# interface.net
KiCad netlist of a schematic drawn in Altium Designer
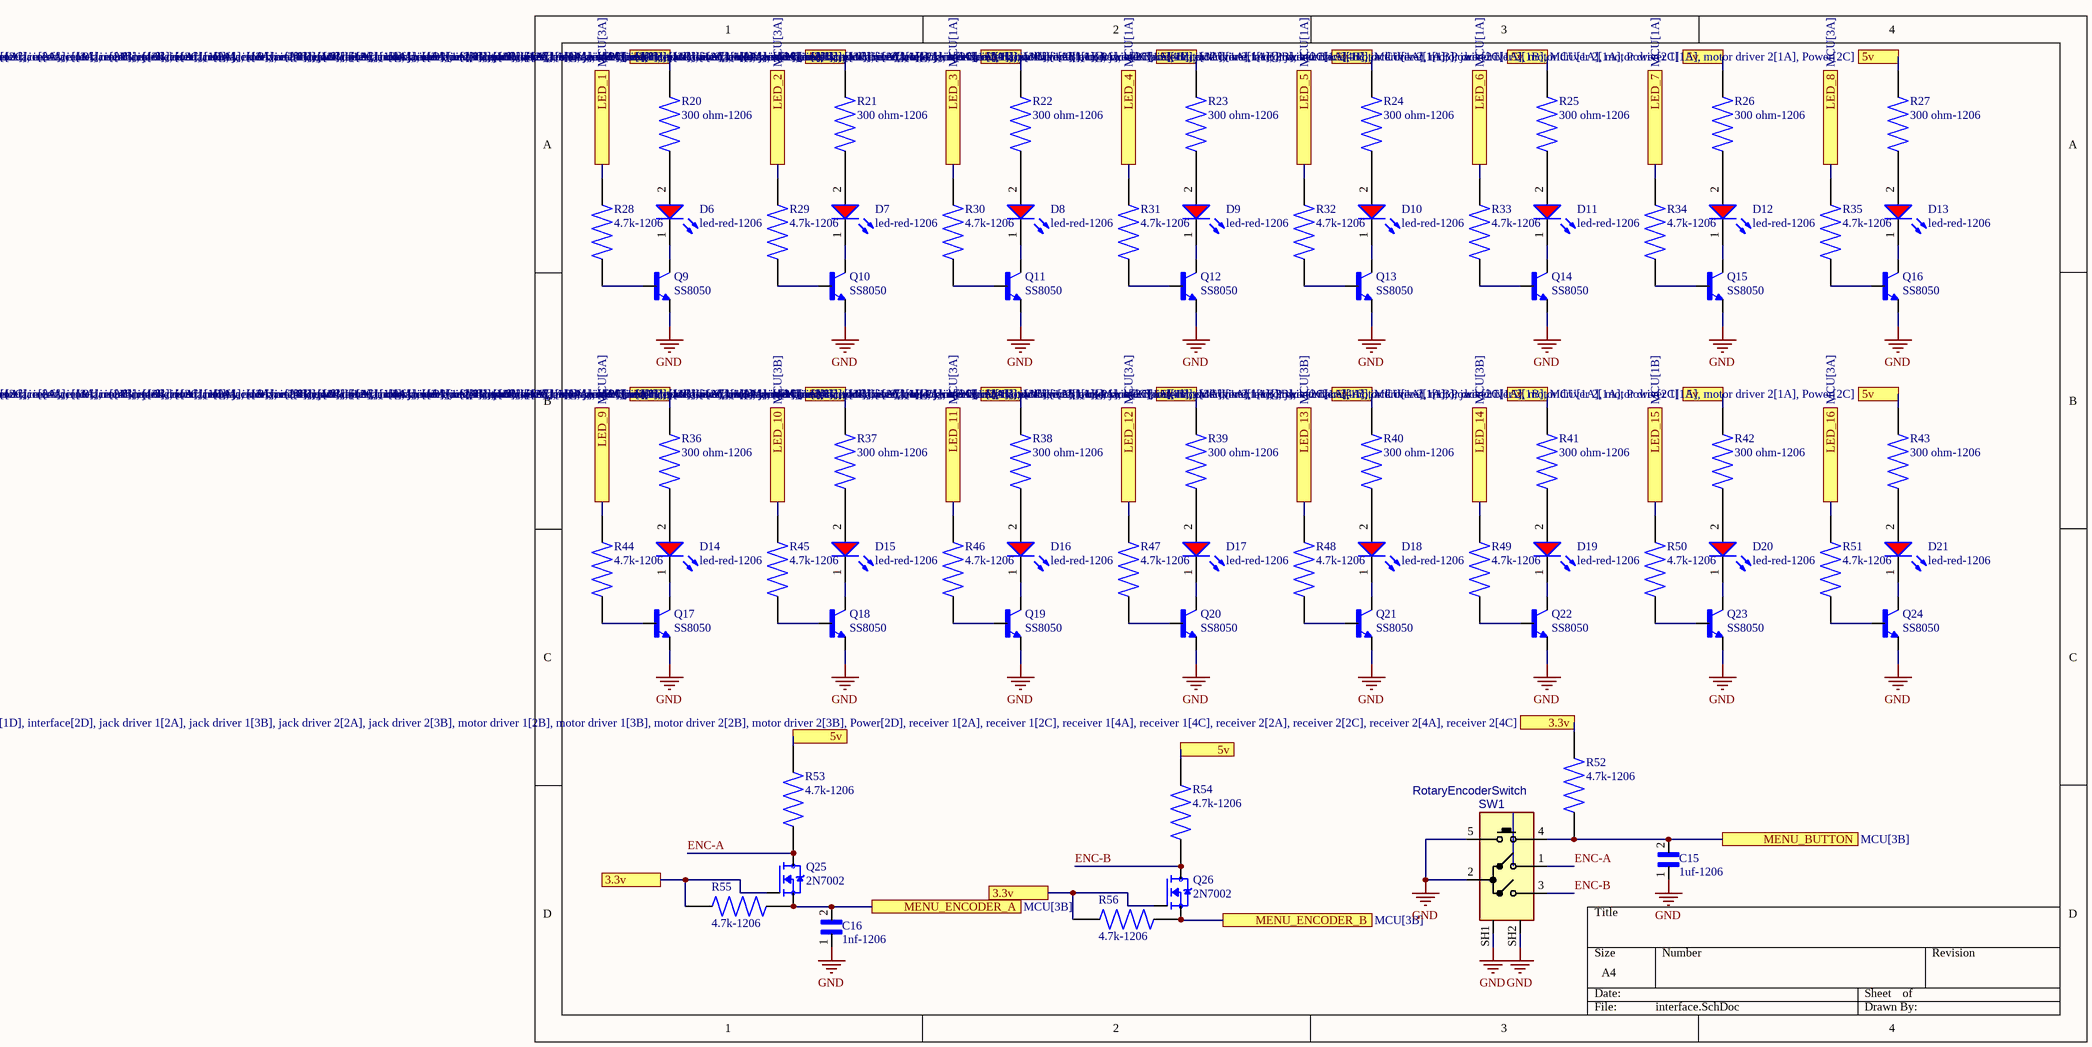
[diagram p0: interface.SchDoc]

(export (version "E")
  (design (tool "Eeschema 10.0.6"))
  (components
    (comp (ref "C15")
      (value "1uf-1206")
      (footprint "CAPC3216X180N")
      (description "1ÂµF Â±20% 50V Ceramic Capacitor X8R 1206 (3216 Metric)")
      (fields (field (name "MF") "TDK") (field (name "MP") "CGA5L3X8R1H105M160AB"))
      (libsource (lib "cap-1206") (part "CGA5L3X8R1H105M160AB"))
    )
    (comp (ref "C16")
      (value "1nf-1206")
      (footprint "CAPC3216X180N")
      (description "1ÂµF Â±20% 50V Ceramic Capacitor X8R 1206 (3216 Metric)")
      (fields (field (name "MF") "TDK") (field (name "MP") "CGA5L3X8R1H105M160AB"))
      (libsource (lib "cap-1206") (part "CGA5L3X8R1H105M160AB"))
    )
    (comp (ref "D6")
      (value "led-red-1206")
      (footprint "WL-SMRW_1206 dome_normal use")
      (description "WL-SMRW Mono-color Reverse mount Waterclear, SMT, size 1206 dome, Red, 2V, 20°")
      (fields
        (field (name "MANUFACTURER PART NUMBER") "156120RS82500")
        (field (name "MANUFACTURER") "Wurth Elektronik")
      )
      (libsource (lib "led-1206") (part "156120RS82500"))
    )
    (comp (ref "D7")
      (value "led-red-1206")
      (footprint "WL-SMRW_1206 dome_normal use")
      (description "WL-SMRW Mono-color Reverse mount Waterclear, SMT, size 1206 dome, Red, 2V, 20°")
      (fields
        (field (name "MANUFACTURER PART NUMBER") "156120RS82500")
        (field (name "MANUFACTURER") "Wurth Elektronik")
      )
      (libsource (lib "led-1206") (part "156120RS82500"))
    )
    (comp (ref "D8")
      (value "led-red-1206")
      (footprint "WL-SMRW_1206 dome_normal use")
      (description "WL-SMRW Mono-color Reverse mount Waterclear, SMT, size 1206 dome, Red, 2V, 20°")
      (fields
        (field (name "MANUFACTURER PART NUMBER") "156120RS82500")
        (field (name "MANUFACTURER") "Wurth Elektronik")
      )
      (libsource (lib "led-1206") (part "156120RS82500"))
    )
    (comp (ref "D9")
      (value "led-red-1206")
      (footprint "WL-SMRW_1206 dome_normal use")
      (description "WL-SMRW Mono-color Reverse mount Waterclear, SMT, size 1206 dome, Red, 2V, 20°")
      (fields
        (field (name "MANUFACTURER PART NUMBER") "156120RS82500")
        (field (name "MANUFACTURER") "Wurth Elektronik")
      )
      (libsource (lib "led-1206") (part "156120RS82500"))
    )
    (comp (ref "D10")
      (value "led-red-1206")
      (footprint "WL-SMRW_1206 dome_normal use")
      (description "WL-SMRW Mono-color Reverse mount Waterclear, SMT, size 1206 dome, Red, 2V, 20°")
      (fields
        (field (name "MANUFACTURER PART NUMBER") "156120RS82500")
        (field (name "MANUFACTURER") "Wurth Elektronik")
      )
      (libsource (lib "led-1206") (part "156120RS82500"))
    )
    (comp (ref "D11")
      (value "led-red-1206")
      (footprint "WL-SMRW_1206 dome_normal use")
      (description "WL-SMRW Mono-color Reverse mount Waterclear, SMT, size 1206 dome, Red, 2V, 20°")
      (fields
        (field (name "MANUFACTURER PART NUMBER") "156120RS82500")
        (field (name "MANUFACTURER") "Wurth Elektronik")
      )
      (libsource (lib "led-1206") (part "156120RS82500"))
    )
    (comp (ref "D12")
      (value "led-red-1206")
      (footprint "WL-SMRW_1206 dome_normal use")
      (description "WL-SMRW Mono-color Reverse mount Waterclear, SMT, size 1206 dome, Red, 2V, 20°")
      (fields
        (field (name "MANUFACTURER PART NUMBER") "156120RS82500")
        (field (name "MANUFACTURER") "Wurth Elektronik")
      )
      (libsource (lib "led-1206") (part "156120RS82500"))
    )
    (comp (ref "D13")
      (value "led-red-1206")
      (footprint "WL-SMRW_1206 dome_normal use")
      (description "WL-SMRW Mono-color Reverse mount Waterclear, SMT, size 1206 dome, Red, 2V, 20°")
      (fields
        (field (name "MANUFACTURER PART NUMBER") "156120RS82500")
        (field (name "MANUFACTURER") "Wurth Elektronik")
      )
      (libsource (lib "led-1206") (part "156120RS82500"))
    )
    (comp (ref "D14")
      (value "led-red-1206")
      (footprint "WL-SMRW_1206 dome_normal use")
      (description "WL-SMRW Mono-color Reverse mount Waterclear, SMT, size 1206 dome, Red, 2V, 20°")
      (fields
        (field (name "MANUFACTURER PART NUMBER") "156120RS82500")
        (field (name "MANUFACTURER") "Wurth Elektronik")
      )
      (libsource (lib "led-1206") (part "156120RS82500"))
    )
    (comp (ref "D15")
      (value "led-red-1206")
      (footprint "WL-SMRW_1206 dome_normal use")
      (description "WL-SMRW Mono-color Reverse mount Waterclear, SMT, size 1206 dome, Red, 2V, 20°")
      (fields
        (field (name "MANUFACTURER PART NUMBER") "156120RS82500")
        (field (name "MANUFACTURER") "Wurth Elektronik")
      )
      (libsource (lib "led-1206") (part "156120RS82500"))
    )
    (comp (ref "D16")
      (value "led-red-1206")
      (footprint "WL-SMRW_1206 dome_normal use")
      (description "WL-SMRW Mono-color Reverse mount Waterclear, SMT, size 1206 dome, Red, 2V, 20°")
      (fields
        (field (name "MANUFACTURER PART NUMBER") "156120RS82500")
        (field (name "MANUFACTURER") "Wurth Elektronik")
      )
      (libsource (lib "led-1206") (part "156120RS82500"))
    )
    (comp (ref "D17")
      (value "led-red-1206")
      (footprint "WL-SMRW_1206 dome_normal use")
      (description "WL-SMRW Mono-color Reverse mount Waterclear, SMT, size 1206 dome, Red, 2V, 20°")
      (fields
        (field (name "MANUFACTURER PART NUMBER") "156120RS82500")
        (field (name "MANUFACTURER") "Wurth Elektronik")
      )
      (libsource (lib "led-1206") (part "156120RS82500"))
    )
    (comp (ref "D18")
      (value "led-red-1206")
      (footprint "WL-SMRW_1206 dome_normal use")
      (description "WL-SMRW Mono-color Reverse mount Waterclear, SMT, size 1206 dome, Red, 2V, 20°")
      (fields
        (field (name "MANUFACTURER PART NUMBER") "156120RS82500")
        (field (name "MANUFACTURER") "Wurth Elektronik")
      )
      (libsource (lib "led-1206") (part "156120RS82500"))
    )
    (comp (ref "D19")
      (value "led-red-1206")
      (footprint "WL-SMRW_1206 dome_normal use")
      (description "WL-SMRW Mono-color Reverse mount Waterclear, SMT, size 1206 dome, Red, 2V, 20°")
      (fields
        (field (name "MANUFACTURER PART NUMBER") "156120RS82500")
        (field (name "MANUFACTURER") "Wurth Elektronik")
      )
      (libsource (lib "led-1206") (part "156120RS82500"))
    )
    (comp (ref "D20")
      (value "led-red-1206")
      (footprint "WL-SMRW_1206 dome_normal use")
      (description "WL-SMRW Mono-color Reverse mount Waterclear, SMT, size 1206 dome, Red, 2V, 20°")
      (fields
        (field (name "MANUFACTURER PART NUMBER") "156120RS82500")
        (field (name "MANUFACTURER") "Wurth Elektronik")
      )
      (libsource (lib "led-1206") (part "156120RS82500"))
    )
    (comp (ref "D21")
      (value "led-red-1206")
      (footprint "WL-SMRW_1206 dome_normal use")
      (description "WL-SMRW Mono-color Reverse mount Waterclear, SMT, size 1206 dome, Red, 2V, 20°")
      (fields
        (field (name "MANUFACTURER PART NUMBER") "156120RS82500")
        (field (name "MANUFACTURER") "Wurth Elektronik")
      )
      (libsource (lib "led-1206") (part "156120RS82500"))
    )
    (comp (ref "Q9")
      (value "SS8050")
      (footprint "TRANS_SS8050-G")
      (description "Bipolar (BJT) Transistor NPN 25 V 1.5 A 100MHz 300 mW Surface Mount SOT-23-3")
      (fields (field (name "DIGI-KEY_PART_NUMBER") "641-1790-2-ND") (field (name "MP") "SS8050G"))
      (libsource (lib "SS8050-G") (part "SS8050-G"))
    )
    (comp (ref "Q10")
      (value "SS8050")
      (footprint "TRANS_SS8050-G")
      (description "Bipolar (BJT) Transistor NPN 25 V 1.5 A 100MHz 300 mW Surface Mount SOT-23-3")
      (fields (field (name "DIGI-KEY_PART_NUMBER") "641-1790-2-ND") (field (name "MP") "SS8050G"))
      (libsource (lib "SS8050-G") (part "SS8050-G"))
    )
    (comp (ref "Q11")
      (value "SS8050")
      (footprint "TRANS_SS8050-G")
      (description "Bipolar (BJT) Transistor NPN 25 V 1.5 A 100MHz 300 mW Surface Mount SOT-23-3")
      (fields (field (name "DIGI-KEY_PART_NUMBER") "641-1790-2-ND") (field (name "MP") "SS8050G"))
      (libsource (lib "SS8050-G") (part "SS8050-G"))
    )
    (comp (ref "Q12")
      (value "SS8050")
      (footprint "TRANS_SS8050-G")
      (description "Bipolar (BJT) Transistor NPN 25 V 1.5 A 100MHz 300 mW Surface Mount SOT-23-3")
      (fields (field (name "DIGI-KEY_PART_NUMBER") "641-1790-2-ND") (field (name "MP") "SS8050G"))
      (libsource (lib "SS8050-G") (part "SS8050-G"))
    )
    (comp (ref "Q13")
      (value "SS8050")
      (footprint "TRANS_SS8050-G")
      (description "Bipolar (BJT) Transistor NPN 25 V 1.5 A 100MHz 300 mW Surface Mount SOT-23-3")
      (fields (field (name "DIGI-KEY_PART_NUMBER") "641-1790-2-ND") (field (name "MP") "SS8050G"))
      (libsource (lib "SS8050-G") (part "SS8050-G"))
    )
    (comp (ref "Q14")
      (value "SS8050")
      (footprint "TRANS_SS8050-G")
      (description "Bipolar (BJT) Transistor NPN 25 V 1.5 A 100MHz 300 mW Surface Mount SOT-23-3")
      (fields (field (name "DIGI-KEY_PART_NUMBER") "641-1790-2-ND") (field (name "MP") "SS8050G"))
      (libsource (lib "SS8050-G") (part "SS8050-G"))
    )
    (comp (ref "Q15")
      (value "SS8050")
      (footprint "TRANS_SS8050-G")
      (description "Bipolar (BJT) Transistor NPN 25 V 1.5 A 100MHz 300 mW Surface Mount SOT-23-3")
      (fields (field (name "DIGI-KEY_PART_NUMBER") "641-1790-2-ND") (field (name "MP") "SS8050G"))
      (libsource (lib "SS8050-G") (part "SS8050-G"))
    )
    (comp (ref "Q16")
      (value "SS8050")
      (footprint "TRANS_SS8050-G")
      (description "Bipolar (BJT) Transistor NPN 25 V 1.5 A 100MHz 300 mW Surface Mount SOT-23-3")
      (fields (field (name "DIGI-KEY_PART_NUMBER") "641-1790-2-ND") (field (name "MP") "SS8050G"))
      (libsource (lib "SS8050-G") (part "SS8050-G"))
    )
    (comp (ref "Q17")
      (value "SS8050")
      (footprint "TRANS_SS8050-G")
      (description "Bipolar (BJT) Transistor NPN 25 V 1.5 A 100MHz 300 mW Surface Mount SOT-23-3")
      (fields (field (name "DIGI-KEY_PART_NUMBER") "641-1790-2-ND") (field (name "MP") "SS8050G"))
      (libsource (lib "SS8050-G") (part "SS8050-G"))
    )
    (comp (ref "Q18")
      (value "SS8050")
      (footprint "TRANS_SS8050-G")
      (description "Bipolar (BJT) Transistor NPN 25 V 1.5 A 100MHz 300 mW Surface Mount SOT-23-3")
      (fields (field (name "DIGI-KEY_PART_NUMBER") "641-1790-2-ND") (field (name "MP") "SS8050G"))
      (libsource (lib "SS8050-G") (part "SS8050-G"))
    )
    (comp (ref "Q19")
      (value "SS8050")
      (footprint "TRANS_SS8050-G")
      (description "Bipolar (BJT) Transistor NPN 25 V 1.5 A 100MHz 300 mW Surface Mount SOT-23-3")
      (fields (field (name "DIGI-KEY_PART_NUMBER") "641-1790-2-ND") (field (name "MP") "SS8050G"))
      (libsource (lib "SS8050-G") (part "SS8050-G"))
    )
    (comp (ref "Q20")
      (value "SS8050")
      (footprint "TRANS_SS8050-G")
      (description "Bipolar (BJT) Transistor NPN 25 V 1.5 A 100MHz 300 mW Surface Mount SOT-23-3")
      (fields (field (name "DIGI-KEY_PART_NUMBER") "641-1790-2-ND") (field (name "MP") "SS8050G"))
      (libsource (lib "SS8050-G") (part "SS8050-G"))
    )
    (comp (ref "Q21")
      (value "SS8050")
      (footprint "TRANS_SS8050-G")
      (description "Bipolar (BJT) Transistor NPN 25 V 1.5 A 100MHz 300 mW Surface Mount SOT-23-3")
      (fields (field (name "DIGI-KEY_PART_NUMBER") "641-1790-2-ND") (field (name "MP") "SS8050G"))
      (libsource (lib "SS8050-G") (part "SS8050-G"))
    )
    (comp (ref "Q22")
      (value "SS8050")
      (footprint "TRANS_SS8050-G")
      (description "Bipolar (BJT) Transistor NPN 25 V 1.5 A 100MHz 300 mW Surface Mount SOT-23-3")
      (fields (field (name "DIGI-KEY_PART_NUMBER") "641-1790-2-ND") (field (name "MP") "SS8050G"))
      (libsource (lib "SS8050-G") (part "SS8050-G"))
    )
    (comp (ref "Q23")
      (value "SS8050")
      (footprint "TRANS_SS8050-G")
      (description "Bipolar (BJT) Transistor NPN 25 V 1.5 A 100MHz 300 mW Surface Mount SOT-23-3")
      (fields (field (name "DIGI-KEY_PART_NUMBER") "641-1790-2-ND") (field (name "MP") "SS8050G"))
      (libsource (lib "SS8050-G") (part "SS8050-G"))
    )
    (comp (ref "Q24")
      (value "SS8050")
      (footprint "TRANS_SS8050-G")
      (description "Bipolar (BJT) Transistor NPN 25 V 1.5 A 100MHz 300 mW Surface Mount SOT-23-3")
      (fields (field (name "DIGI-KEY_PART_NUMBER") "641-1790-2-ND") (field (name "MP") "SS8050G"))
      (libsource (lib "SS8050-G") (part "SS8050-G"))
    )
    (comp (ref "Q25")
      (value "2N7002")
      (footprint "SOT95P240X111-3N")
      (description "N-Channel 60V 280mA (Ta) 350mW (Ta) Surface Mount SOT-23-3 (TO-236)")
      (fields (field (name "MF") "{'manufacturer': u'onsemi'}"))
      (libsource (lib "2N7002-SOT23") (part "2N7002"))
    )
    (comp (ref "Q26")
      (value "2N7002")
      (footprint "SOT95P240X111-3N")
      (description "N-Channel 60V 280mA (Ta) 350mW (Ta) Surface Mount SOT-23-3 (TO-236)")
      (fields (field (name "MF") "{'manufacturer': u'onsemi'}"))
      (libsource (lib "2N7002-SOT23") (part "2N7002"))
    )
    (comp (ref "R20")
      (value "300 ohm-1206")
      (footprint "RESC3015X65N")
      (description "Res Thin Film 1206 10K Ohm 0.1% 1/8W Â±25ppm/Â°C Molded SMD SMD Paper T/R")
      (fields (field (name "MF") "TE Connectivity") (field (name "MP") "CPF1206B10KE1"))
      (libsource (lib "resistor-1206") (part "CPF1206B10KE1"))
    )
    (comp (ref "R21")
      (value "300 ohm-1206")
      (footprint "RESC3015X65N")
      (description "Res Thin Film 1206 10K Ohm 0.1% 1/8W Â±25ppm/Â°C Molded SMD SMD Paper T/R")
      (fields (field (name "MF") "TE Connectivity") (field (name "MP") "CPF1206B10KE1"))
      (libsource (lib "resistor-1206") (part "CPF1206B10KE1"))
    )
    (comp (ref "R22")
      (value "300 ohm-1206")
      (footprint "RESC3015X65N")
      (description "Res Thin Film 1206 10K Ohm 0.1% 1/8W Â±25ppm/Â°C Molded SMD SMD Paper T/R")
      (fields (field (name "MF") "TE Connectivity") (field (name "MP") "CPF1206B10KE1"))
      (libsource (lib "resistor-1206") (part "CPF1206B10KE1"))
    )
    (comp (ref "R23")
      (value "300 ohm-1206")
      (footprint "RESC3015X65N")
      (description "Res Thin Film 1206 10K Ohm 0.1% 1/8W Â±25ppm/Â°C Molded SMD SMD Paper T/R")
      (fields (field (name "MF") "TE Connectivity") (field (name "MP") "CPF1206B10KE1"))
      (libsource (lib "resistor-1206") (part "CPF1206B10KE1"))
    )
    (comp (ref "R24")
      (value "300 ohm-1206")
      (footprint "RESC3015X65N")
      (description "Res Thin Film 1206 10K Ohm 0.1% 1/8W Â±25ppm/Â°C Molded SMD SMD Paper T/R")
      (fields (field (name "MF") "TE Connectivity") (field (name "MP") "CPF1206B10KE1"))
      (libsource (lib "resistor-1206") (part "CPF1206B10KE1"))
    )
    (comp (ref "R25")
      (value "300 ohm-1206")
      (footprint "RESC3015X65N")
      (description "Res Thin Film 1206 10K Ohm 0.1% 1/8W Â±25ppm/Â°C Molded SMD SMD Paper T/R")
      (fields (field (name "MF") "TE Connectivity") (field (name "MP") "CPF1206B10KE1"))
      (libsource (lib "resistor-1206") (part "CPF1206B10KE1"))
    )
    (comp (ref "R26")
      (value "300 ohm-1206")
      (footprint "RESC3015X65N")
      (description "Res Thin Film 1206 10K Ohm 0.1% 1/8W Â±25ppm/Â°C Molded SMD SMD Paper T/R")
      (fields (field (name "MF") "TE Connectivity") (field (name "MP") "CPF1206B10KE1"))
      (libsource (lib "resistor-1206") (part "CPF1206B10KE1"))
    )
    (comp (ref "R27")
      (value "300 ohm-1206")
      (footprint "RESC3015X65N")
      (description "Res Thin Film 1206 10K Ohm 0.1% 1/8W Â±25ppm/Â°C Molded SMD SMD Paper T/R")
      (fields (field (name "MF") "TE Connectivity") (field (name "MP") "CPF1206B10KE1"))
      (libsource (lib "resistor-1206") (part "CPF1206B10KE1"))
    )
    (comp (ref "R28")
      (value "4.7k-1206")
      (footprint "RESC3015X65N")
      (description "Res Thin Film 1206 10K Ohm 0.1% 1/8W Â±25ppm/Â°C Molded SMD SMD Paper T/R")
      (fields (field (name "MF") "TE Connectivity") (field (name "MP") "CPF1206B10KE1"))
      (libsource (lib "resistor-1206") (part "CPF1206B10KE1"))
    )
    (comp (ref "R29")
      (value "4.7k-1206")
      (footprint "RESC3015X65N")
      (description "Res Thin Film 1206 10K Ohm 0.1% 1/8W Â±25ppm/Â°C Molded SMD SMD Paper T/R")
      (fields (field (name "MF") "TE Connectivity") (field (name "MP") "CPF1206B10KE1"))
      (libsource (lib "resistor-1206") (part "CPF1206B10KE1"))
    )
    (comp (ref "R30")
      (value "4.7k-1206")
      (footprint "RESC3015X65N")
      (description "Res Thin Film 1206 10K Ohm 0.1% 1/8W Â±25ppm/Â°C Molded SMD SMD Paper T/R")
      (fields (field (name "MF") "TE Connectivity") (field (name "MP") "CPF1206B10KE1"))
      (libsource (lib "resistor-1206") (part "CPF1206B10KE1"))
    )
    (comp (ref "R31")
      (value "4.7k-1206")
      (footprint "RESC3015X65N")
      (description "Res Thin Film 1206 10K Ohm 0.1% 1/8W Â±25ppm/Â°C Molded SMD SMD Paper T/R")
      (fields (field (name "MF") "TE Connectivity") (field (name "MP") "CPF1206B10KE1"))
      (libsource (lib "resistor-1206") (part "CPF1206B10KE1"))
    )
    (comp (ref "R32")
      (value "4.7k-1206")
      (footprint "RESC3015X65N")
      (description "Res Thin Film 1206 10K Ohm 0.1% 1/8W Â±25ppm/Â°C Molded SMD SMD Paper T/R")
      (fields (field (name "MF") "TE Connectivity") (field (name "MP") "CPF1206B10KE1"))
      (libsource (lib "resistor-1206") (part "CPF1206B10KE1"))
    )
    (comp (ref "R33")
      (value "4.7k-1206")
      (footprint "RESC3015X65N")
      (description "Res Thin Film 1206 10K Ohm 0.1% 1/8W Â±25ppm/Â°C Molded SMD SMD Paper T/R")
      (fields (field (name "MF") "TE Connectivity") (field (name "MP") "CPF1206B10KE1"))
      (libsource (lib "resistor-1206") (part "CPF1206B10KE1"))
    )
    (comp (ref "R34")
      (value "4.7k-1206")
      (footprint "RESC3015X65N")
      (description "Res Thin Film 1206 10K Ohm 0.1% 1/8W Â±25ppm/Â°C Molded SMD SMD Paper T/R")
      (fields (field (name "MF") "TE Connectivity") (field (name "MP") "CPF1206B10KE1"))
      (libsource (lib "resistor-1206") (part "CPF1206B10KE1"))
    )
    (comp (ref "R35")
      (value "4.7k-1206")
      (footprint "RESC3015X65N")
      (description "Res Thin Film 1206 10K Ohm 0.1% 1/8W Â±25ppm/Â°C Molded SMD SMD Paper T/R")
      (fields (field (name "MF") "TE Connectivity") (field (name "MP") "CPF1206B10KE1"))
      (libsource (lib "resistor-1206") (part "CPF1206B10KE1"))
    )
    (comp (ref "R36")
      (value "300 ohm-1206")
      (footprint "RESC3015X65N")
      (description "Res Thin Film 1206 10K Ohm 0.1% 1/8W Â±25ppm/Â°C Molded SMD SMD Paper T/R")
      (fields (field (name "MF") "TE Connectivity") (field (name "MP") "CPF1206B10KE1"))
      (libsource (lib "resistor-1206") (part "CPF1206B10KE1"))
    )
    (comp (ref "R37")
      (value "300 ohm-1206")
      (footprint "RESC3015X65N")
      (description "Res Thin Film 1206 10K Ohm 0.1% 1/8W Â±25ppm/Â°C Molded SMD SMD Paper T/R")
      (fields (field (name "MF") "TE Connectivity") (field (name "MP") "CPF1206B10KE1"))
      (libsource (lib "resistor-1206") (part "CPF1206B10KE1"))
    )
    (comp (ref "R38")
      (value "300 ohm-1206")
      (footprint "RESC3015X65N")
      (description "Res Thin Film 1206 10K Ohm 0.1% 1/8W Â±25ppm/Â°C Molded SMD SMD Paper T/R")
      (fields (field (name "MF") "TE Connectivity") (field (name "MP") "CPF1206B10KE1"))
      (libsource (lib "resistor-1206") (part "CPF1206B10KE1"))
    )
    (comp (ref "R39")
      (value "300 ohm-1206")
      (footprint "RESC3015X65N")
      (description "Res Thin Film 1206 10K Ohm 0.1% 1/8W Â±25ppm/Â°C Molded SMD SMD Paper T/R")
      (fields (field (name "MF") "TE Connectivity") (field (name "MP") "CPF1206B10KE1"))
      (libsource (lib "resistor-1206") (part "CPF1206B10KE1"))
    )
    (comp (ref "R40")
      (value "300 ohm-1206")
      (footprint "RESC3015X65N")
      (description "Res Thin Film 1206 10K Ohm 0.1% 1/8W Â±25ppm/Â°C Molded SMD SMD Paper T/R")
      (fields (field (name "MF") "TE Connectivity") (field (name "MP") "CPF1206B10KE1"))
      (libsource (lib "resistor-1206") (part "CPF1206B10KE1"))
    )
    (comp (ref "R41")
      (value "300 ohm-1206")
      (footprint "RESC3015X65N")
      (description "Res Thin Film 1206 10K Ohm 0.1% 1/8W Â±25ppm/Â°C Molded SMD SMD Paper T/R")
      (fields (field (name "MF") "TE Connectivity") (field (name "MP") "CPF1206B10KE1"))
      (libsource (lib "resistor-1206") (part "CPF1206B10KE1"))
    )
    (comp (ref "R42")
      (value "300 ohm-1206")
      (footprint "RESC3015X65N")
      (description "Res Thin Film 1206 10K Ohm 0.1% 1/8W Â±25ppm/Â°C Molded SMD SMD Paper T/R")
      (fields (field (name "MF") "TE Connectivity") (field (name "MP") "CPF1206B10KE1"))
      (libsource (lib "resistor-1206") (part "CPF1206B10KE1"))
    )
    (comp (ref "R43")
      (value "300 ohm-1206")
      (footprint "RESC3015X65N")
      (description "Res Thin Film 1206 10K Ohm 0.1% 1/8W Â±25ppm/Â°C Molded SMD SMD Paper T/R")
      (fields (field (name "MF") "TE Connectivity") (field (name "MP") "CPF1206B10KE1"))
      (libsource (lib "resistor-1206") (part "CPF1206B10KE1"))
    )
    (comp (ref "R44")
      (value "4.7k-1206")
      (footprint "RESC3015X65N")
      (description "Res Thin Film 1206 10K Ohm 0.1% 1/8W Â±25ppm/Â°C Molded SMD SMD Paper T/R")
      (fields (field (name "MF") "TE Connectivity") (field (name "MP") "CPF1206B10KE1"))
      (libsource (lib "resistor-1206") (part "CPF1206B10KE1"))
    )
    (comp (ref "R45")
      (value "4.7k-1206")
      (footprint "RESC3015X65N")
      (description "Res Thin Film 1206 10K Ohm 0.1% 1/8W Â±25ppm/Â°C Molded SMD SMD Paper T/R")
      (fields (field (name "MF") "TE Connectivity") (field (name "MP") "CPF1206B10KE1"))
      (libsource (lib "resistor-1206") (part "CPF1206B10KE1"))
    )
    (comp (ref "R46")
      (value "4.7k-1206")
      (footprint "RESC3015X65N")
      (description "Res Thin Film 1206 10K Ohm 0.1% 1/8W Â±25ppm/Â°C Molded SMD SMD Paper T/R")
      (fields (field (name "MF") "TE Connectivity") (field (name "MP") "CPF1206B10KE1"))
      (libsource (lib "resistor-1206") (part "CPF1206B10KE1"))
    )
    (comp (ref "R47")
      (value "4.7k-1206")
      (footprint "RESC3015X65N")
      (description "Res Thin Film 1206 10K Ohm 0.1% 1/8W Â±25ppm/Â°C Molded SMD SMD Paper T/R")
      (fields (field (name "MF") "TE Connectivity") (field (name "MP") "CPF1206B10KE1"))
      (libsource (lib "resistor-1206") (part "CPF1206B10KE1"))
    )
    (comp (ref "R48")
      (value "4.7k-1206")
      (footprint "RESC3015X65N")
      (description "Res Thin Film 1206 10K Ohm 0.1% 1/8W Â±25ppm/Â°C Molded SMD SMD Paper T/R")
      (fields (field (name "MF") "TE Connectivity") (field (name "MP") "CPF1206B10KE1"))
      (libsource (lib "resistor-1206") (part "CPF1206B10KE1"))
    )
    (comp (ref "R49")
      (value "4.7k-1206")
      (footprint "RESC3015X65N")
      (description "Res Thin Film 1206 10K Ohm 0.1% 1/8W Â±25ppm/Â°C Molded SMD SMD Paper T/R")
      (fields (field (name "MF") "TE Connectivity") (field (name "MP") "CPF1206B10KE1"))
      (libsource (lib "resistor-1206") (part "CPF1206B10KE1"))
    )
    (comp (ref "R50")
      (value "4.7k-1206")
      (footprint "RESC3015X65N")
      (description "Res Thin Film 1206 10K Ohm 0.1% 1/8W Â±25ppm/Â°C Molded SMD SMD Paper T/R")
      (fields (field (name "MF") "TE Connectivity") (field (name "MP") "CPF1206B10KE1"))
      (libsource (lib "resistor-1206") (part "CPF1206B10KE1"))
    )
    (comp (ref "R51")
      (value "4.7k-1206")
      (footprint "RESC3015X65N")
      (description "Res Thin Film 1206 10K Ohm 0.1% 1/8W Â±25ppm/Â°C Molded SMD SMD Paper T/R")
      (fields (field (name "MF") "TE Connectivity") (field (name "MP") "CPF1206B10KE1"))
      (libsource (lib "resistor-1206") (part "CPF1206B10KE1"))
    )
    (comp (ref "R52")
      (value "4.7k-1206")
      (footprint "RESC3015X65N")
      (description "Res Thin Film 1206 10K Ohm 0.1% 1/8W Â±25ppm/Â°C Molded SMD SMD Paper T/R")
      (fields (field (name "MF") "TE Connectivity") (field (name "MP") "CPF1206B10KE1"))
      (libsource (lib "resistor-1206") (part "CPF1206B10KE1"))
    )
    (comp (ref "R53")
      (value "4.7k-1206")
      (footprint "RESC3015X65N")
      (description "Res Thin Film 1206 10K Ohm 0.1% 1/8W Â±25ppm/Â°C Molded SMD SMD Paper T/R")
      (fields (field (name "MF") "TE Connectivity") (field (name "MP") "CPF1206B10KE1"))
      (libsource (lib "resistor-1206") (part "CPF1206B10KE1"))
    )
    (comp (ref "R54")
      (value "4.7k-1206")
      (footprint "RESC3015X65N")
      (description "Res Thin Film 1206 10K Ohm 0.1% 1/8W Â±25ppm/Â°C Molded SMD SMD Paper T/R")
      (fields (field (name "MF") "TE Connectivity") (field (name "MP") "CPF1206B10KE1"))
      (libsource (lib "resistor-1206") (part "CPF1206B10KE1"))
    )
    (comp (ref "R55")
      (value "4.7k-1206")
      (footprint "RESC3015X65N")
      (description "Res Thin Film 1206 10K Ohm 0.1% 1/8W Â±25ppm/Â°C Molded SMD SMD Paper T/R")
      (fields (field (name "MF") "TE Connectivity") (field (name "MP") "CPF1206B10KE1"))
      (libsource (lib "resistor-1206") (part "CPF1206B10KE1"))
    )
    (comp (ref "R56")
      (value "4.7k-1206")
      (footprint "RESC3015X65N")
      (description "Res Thin Film 1206 10K Ohm 0.1% 1/8W Â±25ppm/Â°C Molded SMD SMD Paper T/R")
      (fields (field (name "MF") "TE Connectivity") (field (name "MP") "CPF1206B10KE1"))
      (libsource (lib "resistor-1206") (part "CPF1206B10KE1"))
    )
    (comp (ref "SW1")
      (value "RotaryEncoderSwitch")
      (footprint "SWROT_11MM")
      (description "SWITCH, ROTARY Encoder, 11mm Metal Shaft")
      (fields (field (name "MANF") "Alpha") (field (name "MANF_PART#") "RE111F-41B3N-15F-20P"))
      (libsource (lib "rotary encoder") (part "SWROT_11MM"))
    )
  )
  (nets
    (net (code "1") (name "/3.3v") (class "Default")
      (node (ref "Q25") (pin "1") (pinfunction "G_1") (pintype "passive"))
      (node (ref "Q26") (pin "1") (pinfunction "G_1") (pintype "passive"))
      (node (ref "R52") (pin "2") (pinfunction "2_2") (pintype "passive"))
      (node (ref "R55") (pin "1") (pinfunction "1_1") (pintype "passive"))
      (node (ref "R56") (pin "2") (pinfunction "2_2") (pintype "passive"))
    )
    (net (code "2") (name "/5v") (class "Default")
      (node (ref "R20") (pin "2") (pinfunction "2_2") (pintype "passive"))
      (node (ref "R21") (pin "2") (pinfunction "2_2") (pintype "passive"))
      (node (ref "R22") (pin "2") (pinfunction "2_2") (pintype "passive"))
      (node (ref "R23") (pin "2") (pinfunction "2_2") (pintype "passive"))
      (node (ref "R24") (pin "2") (pinfunction "2_2") (pintype "passive"))
      (node (ref "R25") (pin "2") (pinfunction "2_2") (pintype "passive"))
      (node (ref "R26") (pin "2") (pinfunction "2_2") (pintype "passive"))
      (node (ref "R27") (pin "2") (pinfunction "2_2") (pintype "passive"))
      (node (ref "R36") (pin "2") (pinfunction "2_2") (pintype "passive"))
      (node (ref "R37") (pin "2") (pinfunction "2_2") (pintype "passive"))
      (node (ref "R38") (pin "2") (pinfunction "2_2") (pintype "passive"))
      (node (ref "R39") (pin "2") (pinfunction "2_2") (pintype "passive"))
      (node (ref "R40") (pin "2") (pinfunction "2_2") (pintype "passive"))
      (node (ref "R41") (pin "2") (pinfunction "2_2") (pintype "passive"))
      (node (ref "R42") (pin "2") (pinfunction "2_2") (pintype "passive"))
      (node (ref "R43") (pin "2") (pinfunction "2_2") (pintype "passive"))
      (node (ref "R53") (pin "2") (pinfunction "2_2") (pintype "passive"))
      (node (ref "R54") (pin "2") (pinfunction "2_2") (pintype "passive"))
    )
    (net (code "3") (name "/ENC-A") (class "Default")
      (node (ref "Q25") (pin "3") (pinfunction "D_3") (pintype "passive"))
      (node (ref "R53") (pin "1") (pinfunction "1_1") (pintype "passive"))
      (node (ref "SW1") (pin "1") (pinfunction "A_1") (pintype "passive"))
    )
    (net (code "4") (name "/ENC-B") (class "Default")
      (node (ref "Q26") (pin "3") (pinfunction "D_3") (pintype "passive"))
      (node (ref "R54") (pin "1") (pinfunction "1_1") (pintype "passive"))
      (node (ref "SW1") (pin "3") (pinfunction "B_3") (pintype "passive"))
    )
    (net (code "5") (name "/LED_1") (class "Default")
      (node (ref "R28") (pin "2") (pinfunction "2_2") (pintype "passive"))
    )
    (net (code "6") (name "/LED_2") (class "Default")
      (node (ref "R29") (pin "2") (pinfunction "2_2") (pintype "passive"))
    )
    (net (code "7") (name "/LED_3") (class "Default")
      (node (ref "R30") (pin "2") (pinfunction "2_2") (pintype "passive"))
    )
    (net (code "8") (name "/LED_4") (class "Default")
      (node (ref "R31") (pin "2") (pinfunction "2_2") (pintype "passive"))
    )
    (net (code "9") (name "/LED_5") (class "Default")
      (node (ref "R32") (pin "2") (pinfunction "2_2") (pintype "passive"))
    )
    (net (code "10") (name "/LED_6") (class "Default")
      (node (ref "R33") (pin "2") (pinfunction "2_2") (pintype "passive"))
    )
    (net (code "11") (name "/LED_7") (class "Default")
      (node (ref "R34") (pin "2") (pinfunction "2_2") (pintype "passive"))
    )
    (net (code "12") (name "/LED_8") (class "Default")
      (node (ref "R35") (pin "2") (pinfunction "2_2") (pintype "passive"))
    )
    (net (code "13") (name "/LED_9") (class "Default")
      (node (ref "R44") (pin "2") (pinfunction "2_2") (pintype "passive"))
    )
    (net (code "14") (name "/LED_10") (class "Default")
      (node (ref "R45") (pin "2") (pinfunction "2_2") (pintype "passive"))
    )
    (net (code "15") (name "/LED_11") (class "Default")
      (node (ref "R46") (pin "2") (pinfunction "2_2") (pintype "passive"))
    )
    (net (code "16") (name "/LED_12") (class "Default")
      (node (ref "R47") (pin "2") (pinfunction "2_2") (pintype "passive"))
    )
    (net (code "17") (name "/LED_13") (class "Default")
      (node (ref "R48") (pin "2") (pinfunction "2_2") (pintype "passive"))
    )
    (net (code "18") (name "/LED_14") (class "Default")
      (node (ref "R49") (pin "2") (pinfunction "2_2") (pintype "passive"))
    )
    (net (code "19") (name "/LED_15") (class "Default")
      (node (ref "R50") (pin "2") (pinfunction "2_2") (pintype "passive"))
    )
    (net (code "20") (name "/LED_16") (class "Default")
      (node (ref "R51") (pin "2") (pinfunction "2_2") (pintype "passive"))
    )
    (net (code "21") (name "/MENU_BUTTON") (class "Default")
      (node (ref "C15") (pin "2") (pinfunction "2_2") (pintype "passive"))
      (node (ref "R52") (pin "1") (pinfunction "1_1") (pintype "passive"))
      (node (ref "SW1") (pin "4") (pinfunction "E_4") (pintype "passive"))
    )
    (net (code "22") (name "/MENU_ENCODER_A") (class "Default")
      (node (ref "C16") (pin "2") (pinfunction "2_2") (pintype "passive"))
      (node (ref "Q25") (pin "2") (pinfunction "S_2") (pintype "passive"))
      (node (ref "R55") (pin "2") (pinfunction "2_2") (pintype "passive"))
    )
    (net (code "23") (name "/MENU_ENCODER_B") (class "Default")
      (node (ref "Q26") (pin "2") (pinfunction "S_2") (pintype "passive"))
      (node (ref "R56") (pin "1") (pinfunction "1_1") (pintype "passive"))
    )
    (net (code "24") (name "GND") (class "Default")
      (node (ref "C15") (pin "1") (pinfunction "1_1") (pintype "passive"))
      (node (ref "C16") (pin "1") (pinfunction "1_1") (pintype "passive"))
      (node (ref "Q10") (pin "2") (pinfunction "E_2") (pintype "passive"))
      (node (ref "Q11") (pin "2") (pinfunction "E_2") (pintype "passive"))
      (node (ref "Q12") (pin "2") (pinfunction "E_2") (pintype "passive"))
      (node (ref "Q13") (pin "2") (pinfunction "E_2") (pintype "passive"))
      (node (ref "Q14") (pin "2") (pinfunction "E_2") (pintype "passive"))
      (node (ref "Q15") (pin "2") (pinfunction "E_2") (pintype "passive"))
      (node (ref "Q16") (pin "2") (pinfunction "E_2") (pintype "passive"))
      (node (ref "Q17") (pin "2") (pinfunction "E_2") (pintype "passive"))
      (node (ref "Q18") (pin "2") (pinfunction "E_2") (pintype "passive"))
      (node (ref "Q19") (pin "2") (pinfunction "E_2") (pintype "passive"))
      (node (ref "Q20") (pin "2") (pinfunction "E_2") (pintype "passive"))
      (node (ref "Q21") (pin "2") (pinfunction "E_2") (pintype "passive"))
      (node (ref "Q22") (pin "2") (pinfunction "E_2") (pintype "passive"))
      (node (ref "Q23") (pin "2") (pinfunction "E_2") (pintype "passive"))
      (node (ref "Q24") (pin "2") (pinfunction "E_2") (pintype "passive"))
      (node (ref "Q9") (pin "2") (pinfunction "E_2") (pintype "passive"))
      (node (ref "SW1") (pin "2") (pinfunction "C_2") (pintype "passive"))
      (node (ref "SW1") (pin "5") (pinfunction "D_5") (pintype "passive"))
      (node (ref "SW1") (pin "SH1") (pinfunction "SH1_SH1") (pintype "passive"))
      (node (ref "SW1") (pin "SH2") (pinfunction "SH2_SH2") (pintype "passive"))
    )
    (net (code "25") (name "Net-(D6-A)") (class "Default")
      (node (ref "D6") (pin "2") (pinfunction "A_2") (pintype "passive"))
      (node (ref "R20") (pin "1") (pinfunction "1_1") (pintype "passive"))
    )
    (net (code "26") (name "Net-(D6-K)") (class "Default")
      (node (ref "D6") (pin "1") (pinfunction "K_1") (pintype "passive"))
      (node (ref "Q9") (pin "3") (pinfunction "C_3") (pintype "passive"))
    )
    (net (code "27") (name "Net-(D7-A)") (class "Default")
      (node (ref "D7") (pin "2") (pinfunction "A_2") (pintype "passive"))
      (node (ref "R21") (pin "1") (pinfunction "1_1") (pintype "passive"))
    )
    (net (code "28") (name "Net-(D7-K)") (class "Default")
      (node (ref "D7") (pin "1") (pinfunction "K_1") (pintype "passive"))
      (node (ref "Q10") (pin "3") (pinfunction "C_3") (pintype "passive"))
    )
    (net (code "29") (name "Net-(D8-A)") (class "Default")
      (node (ref "D8") (pin "2") (pinfunction "A_2") (pintype "passive"))
      (node (ref "R22") (pin "1") (pinfunction "1_1") (pintype "passive"))
    )
    (net (code "30") (name "Net-(D8-K)") (class "Default")
      (node (ref "D8") (pin "1") (pinfunction "K_1") (pintype "passive"))
      (node (ref "Q11") (pin "3") (pinfunction "C_3") (pintype "passive"))
    )
    (net (code "31") (name "Net-(D9-A)") (class "Default")
      (node (ref "D9") (pin "2") (pinfunction "A_2") (pintype "passive"))
      (node (ref "R23") (pin "1") (pinfunction "1_1") (pintype "passive"))
    )
    (net (code "32") (name "Net-(D9-K)") (class "Default")
      (node (ref "D9") (pin "1") (pinfunction "K_1") (pintype "passive"))
      (node (ref "Q12") (pin "3") (pinfunction "C_3") (pintype "passive"))
    )
    (net (code "33") (name "Net-(D10-A)") (class "Default")
      (node (ref "D10") (pin "2") (pinfunction "A_2") (pintype "passive"))
      (node (ref "R24") (pin "1") (pinfunction "1_1") (pintype "passive"))
    )
    (net (code "34") (name "Net-(D10-K)") (class "Default")
      (node (ref "D10") (pin "1") (pinfunction "K_1") (pintype "passive"))
      (node (ref "Q13") (pin "3") (pinfunction "C_3") (pintype "passive"))
    )
    (net (code "35") (name "Net-(D11-A)") (class "Default")
      (node (ref "D11") (pin "2") (pinfunction "A_2") (pintype "passive"))
      (node (ref "R25") (pin "1") (pinfunction "1_1") (pintype "passive"))
    )
    (net (code "36") (name "Net-(D11-K)") (class "Default")
      (node (ref "D11") (pin "1") (pinfunction "K_1") (pintype "passive"))
      (node (ref "Q14") (pin "3") (pinfunction "C_3") (pintype "passive"))
    )
    (net (code "37") (name "Net-(D12-A)") (class "Default")
      (node (ref "D12") (pin "2") (pinfunction "A_2") (pintype "passive"))
      (node (ref "R26") (pin "1") (pinfunction "1_1") (pintype "passive"))
    )
    (net (code "38") (name "Net-(D12-K)") (class "Default")
      (node (ref "D12") (pin "1") (pinfunction "K_1") (pintype "passive"))
      (node (ref "Q15") (pin "3") (pinfunction "C_3") (pintype "passive"))
    )
    (net (code "39") (name "Net-(D13-A)") (class "Default")
      (node (ref "D13") (pin "2") (pinfunction "A_2") (pintype "passive"))
      (node (ref "R27") (pin "1") (pinfunction "1_1") (pintype "passive"))
    )
    (net (code "40") (name "Net-(D13-K)") (class "Default")
      (node (ref "D13") (pin "1") (pinfunction "K_1") (pintype "passive"))
      (node (ref "Q16") (pin "3") (pinfunction "C_3") (pintype "passive"))
    )
    (net (code "41") (name "Net-(D14-A)") (class "Default")
      (node (ref "D14") (pin "2") (pinfunction "A_2") (pintype "passive"))
      (node (ref "R36") (pin "1") (pinfunction "1_1") (pintype "passive"))
    )
    (net (code "42") (name "Net-(D14-K)") (class "Default")
      (node (ref "D14") (pin "1") (pinfunction "K_1") (pintype "passive"))
      (node (ref "Q17") (pin "3") (pinfunction "C_3") (pintype "passive"))
    )
    (net (code "43") (name "Net-(D15-A)") (class "Default")
      (node (ref "D15") (pin "2") (pinfunction "A_2") (pintype "passive"))
      (node (ref "R37") (pin "1") (pinfunction "1_1") (pintype "passive"))
    )
    (net (code "44") (name "Net-(D15-K)") (class "Default")
      (node (ref "D15") (pin "1") (pinfunction "K_1") (pintype "passive"))
      (node (ref "Q18") (pin "3") (pinfunction "C_3") (pintype "passive"))
    )
    (net (code "45") (name "Net-(D16-A)") (class "Default")
      (node (ref "D16") (pin "2") (pinfunction "A_2") (pintype "passive"))
      (node (ref "R38") (pin "1") (pinfunction "1_1") (pintype "passive"))
    )
    (net (code "46") (name "Net-(D16-K)") (class "Default")
      (node (ref "D16") (pin "1") (pinfunction "K_1") (pintype "passive"))
      (node (ref "Q19") (pin "3") (pinfunction "C_3") (pintype "passive"))
    )
    (net (code "47") (name "Net-(D17-A)") (class "Default")
      (node (ref "D17") (pin "2") (pinfunction "A_2") (pintype "passive"))
      (node (ref "R39") (pin "1") (pinfunction "1_1") (pintype "passive"))
    )
    (net (code "48") (name "Net-(D17-K)") (class "Default")
      (node (ref "D17") (pin "1") (pinfunction "K_1") (pintype "passive"))
      (node (ref "Q20") (pin "3") (pinfunction "C_3") (pintype "passive"))
    )
    (net (code "49") (name "Net-(D18-A)") (class "Default")
      (node (ref "D18") (pin "2") (pinfunction "A_2") (pintype "passive"))
      (node (ref "R40") (pin "1") (pinfunction "1_1") (pintype "passive"))
    )
    (net (code "50") (name "Net-(D18-K)") (class "Default")
      (node (ref "D18") (pin "1") (pinfunction "K_1") (pintype "passive"))
      (node (ref "Q21") (pin "3") (pinfunction "C_3") (pintype "passive"))
    )
    (net (code "51") (name "Net-(D19-A)") (class "Default")
      (node (ref "D19") (pin "2") (pinfunction "A_2") (pintype "passive"))
      (node (ref "R41") (pin "1") (pinfunction "1_1") (pintype "passive"))
    )
    (net (code "52") (name "Net-(D19-K)") (class "Default")
      (node (ref "D19") (pin "1") (pinfunction "K_1") (pintype "passive"))
      (node (ref "Q22") (pin "3") (pinfunction "C_3") (pintype "passive"))
    )
    (net (code "53") (name "Net-(D20-A)") (class "Default")
      (node (ref "D20") (pin "2") (pinfunction "A_2") (pintype "passive"))
      (node (ref "R42") (pin "1") (pinfunction "1_1") (pintype "passive"))
    )
    (net (code "54") (name "Net-(D20-K)") (class "Default")
      (node (ref "D20") (pin "1") (pinfunction "K_1") (pintype "passive"))
      (node (ref "Q23") (pin "3") (pinfunction "C_3") (pintype "passive"))
    )
    (net (code "55") (name "Net-(D21-A)") (class "Default")
      (node (ref "D21") (pin "2") (pinfunction "A_2") (pintype "passive"))
      (node (ref "R43") (pin "1") (pinfunction "1_1") (pintype "passive"))
    )
    (net (code "56") (name "Net-(D21-K)") (class "Default")
      (node (ref "D21") (pin "1") (pinfunction "K_1") (pintype "passive"))
      (node (ref "Q24") (pin "3") (pinfunction "C_3") (pintype "passive"))
    )
    (net (code "57") (name "Net-(Q9-B)") (class "Default")
      (node (ref "Q9") (pin "1") (pinfunction "B_1") (pintype "passive"))
      (node (ref "R28") (pin "1") (pinfunction "1_1") (pintype "passive"))
    )
    (net (code "58") (name "Net-(Q10-B)") (class "Default")
      (node (ref "Q10") (pin "1") (pinfunction "B_1") (pintype "passive"))
      (node (ref "R29") (pin "1") (pinfunction "1_1") (pintype "passive"))
    )
    (net (code "59") (name "Net-(Q11-B)") (class "Default")
      (node (ref "Q11") (pin "1") (pinfunction "B_1") (pintype "passive"))
      (node (ref "R30") (pin "1") (pinfunction "1_1") (pintype "passive"))
    )
    (net (code "60") (name "Net-(Q12-B)") (class "Default")
      (node (ref "Q12") (pin "1") (pinfunction "B_1") (pintype "passive"))
      (node (ref "R31") (pin "1") (pinfunction "1_1") (pintype "passive"))
    )
    (net (code "61") (name "Net-(Q13-B)") (class "Default")
      (node (ref "Q13") (pin "1") (pinfunction "B_1") (pintype "passive"))
      (node (ref "R32") (pin "1") (pinfunction "1_1") (pintype "passive"))
    )
    (net (code "62") (name "Net-(Q14-B)") (class "Default")
      (node (ref "Q14") (pin "1") (pinfunction "B_1") (pintype "passive"))
      (node (ref "R33") (pin "1") (pinfunction "1_1") (pintype "passive"))
    )
    (net (code "63") (name "Net-(Q15-B)") (class "Default")
      (node (ref "Q15") (pin "1") (pinfunction "B_1") (pintype "passive"))
      (node (ref "R34") (pin "1") (pinfunction "1_1") (pintype "passive"))
    )
    (net (code "64") (name "Net-(Q16-B)") (class "Default")
      (node (ref "Q16") (pin "1") (pinfunction "B_1") (pintype "passive"))
      (node (ref "R35") (pin "1") (pinfunction "1_1") (pintype "passive"))
    )
    (net (code "65") (name "Net-(Q17-B)") (class "Default")
      (node (ref "Q17") (pin "1") (pinfunction "B_1") (pintype "passive"))
      (node (ref "R44") (pin "1") (pinfunction "1_1") (pintype "passive"))
    )
    (net (code "66") (name "Net-(Q18-B)") (class "Default")
      (node (ref "Q18") (pin "1") (pinfunction "B_1") (pintype "passive"))
      (node (ref "R45") (pin "1") (pinfunction "1_1") (pintype "passive"))
    )
    (net (code "67") (name "Net-(Q19-B)") (class "Default")
      (node (ref "Q19") (pin "1") (pinfunction "B_1") (pintype "passive"))
      (node (ref "R46") (pin "1") (pinfunction "1_1") (pintype "passive"))
    )
    (net (code "68") (name "Net-(Q20-B)") (class "Default")
      (node (ref "Q20") (pin "1") (pinfunction "B_1") (pintype "passive"))
      (node (ref "R47") (pin "1") (pinfunction "1_1") (pintype "passive"))
    )
    (net (code "69") (name "Net-(Q21-B)") (class "Default")
      (node (ref "Q21") (pin "1") (pinfunction "B_1") (pintype "passive"))
      (node (ref "R48") (pin "1") (pinfunction "1_1") (pintype "passive"))
    )
    (net (code "70") (name "Net-(Q22-B)") (class "Default")
      (node (ref "Q22") (pin "1") (pinfunction "B_1") (pintype "passive"))
      (node (ref "R49") (pin "1") (pinfunction "1_1") (pintype "passive"))
    )
    (net (code "71") (name "Net-(Q23-B)") (class "Default")
      (node (ref "Q23") (pin "1") (pinfunction "B_1") (pintype "passive"))
      (node (ref "R50") (pin "1") (pinfunction "1_1") (pintype "passive"))
    )
    (net (code "72") (name "Net-(Q24-B)") (class "Default")
      (node (ref "Q24") (pin "1") (pinfunction "B_1") (pintype "passive"))
      (node (ref "R51") (pin "1") (pinfunction "1_1") (pintype "passive"))
    )
  )
)
